# 3V3_Supply.net
KiCad netlist of a schematic drawn in Altium Designer
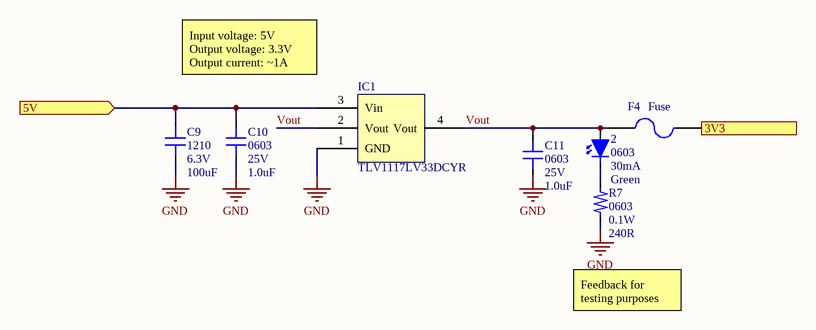
[diagram p0: 3V3_Supply.SchDoc]

(export (version "E")
  (design (tool "Eeschema 10.0.6"))
  (components
    (comp (ref "2")
      (value "0603")
      (footprint "LED_0603")
      (fields
        (field (name "PART NUMBER") "FYLS-0603UGC")
        (field (name "TOLERANCE") "5%")
        (field (name "RATING") "30mA")
        (field (name "ALTIUM_VALUE") "Green")
      )
      (libsource (lib "Components") (part "Diode_LED"))
    )
    (comp (ref "C9")
      (value "1210")
      (footprint "C_1210")
      (fields
        (field (name "TOLERANCE") "10%")
        (field (name "PART NUMBER") "885012109004")
        (field (name "RATING") "6.3V")
        (field (name "ALTIUM_VALUE") "100uF")
      )
      (libsource (lib "Components") (part "Capacitor_Chip"))
    )
    (comp (ref "C10")
      (value "0603")
      (footprint "C_0603")
      (fields
        (field (name "TOLERANCE") "10%")
        (field (name "PART NUMBER") "CL10A105KA8NNNC")
        (field (name "RATING") "25V")
        (field (name "ALTIUM_VALUE") "1.0uF")
      )
      (libsource (lib "Components") (part "Capacitor_Chip"))
    )
    (comp (ref "C11")
      (value "0603")
      (footprint "C_0603")
      (fields
        (field (name "TOLERANCE") "10%")
        (field (name "PART NUMBER") "CL10A105KA8NNNC")
        (field (name "RATING") "25V")
        (field (name "ALTIUM_VALUE") "1.0uF")
      )
      (libsource (lib "Components") (part "Capacitor_Chip"))
    )
    (comp (ref "F4")
      (value "Fuse")
      (footprint "Components:FUSE_1206")
      (fields (field (name "PART NUMBER") "1206SFS100F/63-2") (field (name "NI PART NUMBER") "766260-01"))
      (libsource (lib "Components") (part "Fuse"))
    )
    (comp (ref "IC1")
      (value "TLV1117LV33DCYR")
      (footprint "SOT-223")
      (description "Single Output LDO")
      (libsource (lib "Components") (part "TLV1117"))
    )
    (comp (ref "R7")
      (value "0603")
      (footprint "R_0603")
      (fields
        (field (name "TOLERANCE") "5%")
        (field (name "PART NUMBER") "CR-03JL7--240R")
        (field (name "RATING") "0.1W")
        (field (name "ALTIUM_VALUE") "240R")
        (field (name "NI PART NUMBER") "612640-01")
      )
      (libsource (lib "Components") (part "Resistor_Chip"))
    )
  )
  (nets
    (net (code "1") (name "/3V3") (class "Default")
      (node (ref "F4") (pin "2") (pinfunction "2_2") (pintype "passive"))
    )
    (net (code "2") (name "/5V") (class "Default")
      (node (ref "C10") (pin "2") (pinfunction "C2_2") (pintype "passive"))
      (node (ref "C9") (pin "2") (pinfunction "C2_2") (pintype "passive"))
      (node (ref "IC1") (pin "3") (pinfunction "Vin_3") (pintype "passive"))
    )
    (net (code "3") (name "/Vout") (class "Default")
      (node (ref "2") (pin "2") (pinfunction "DA_2") (pintype "passive"))
      (node (ref "C11") (pin "2") (pinfunction "C2_2") (pintype "passive"))
      (node (ref "F4") (pin "1") (pinfunction "1_1") (pintype "passive"))
      (node (ref "IC1") (pin "2") (pinfunction "Vout_2") (pintype "passive"))
      (node (ref "IC1") (pin "4") (pinfunction "Vout_4") (pintype "passive"))
    )
    (net (code "4") (name "GND") (class "Default")
      (node (ref "C10") (pin "1") (pinfunction "C1_1") (pintype "passive"))
      (node (ref "C11") (pin "1") (pinfunction "C1_1") (pintype "passive"))
      (node (ref "C9") (pin "1") (pinfunction "C1_1") (pintype "passive"))
      (node (ref "IC1") (pin "1") (pinfunction "GND_1") (pintype "passive"))
      (node (ref "R7") (pin "1") (pinfunction "R1_1") (pintype "passive"))
    )
    (net (code "5") (name "Net-(2-DC)") (class "Default")
      (node (ref "2") (pin "1") (pinfunction "DC_1") (pintype "passive"))
      (node (ref "R7") (pin "2") (pinfunction "R2_2") (pintype "passive"))
    )
  )
)
